# Arduino-DUE-V03A.net
KiCad netlist of a schematic drawn in EAGLE
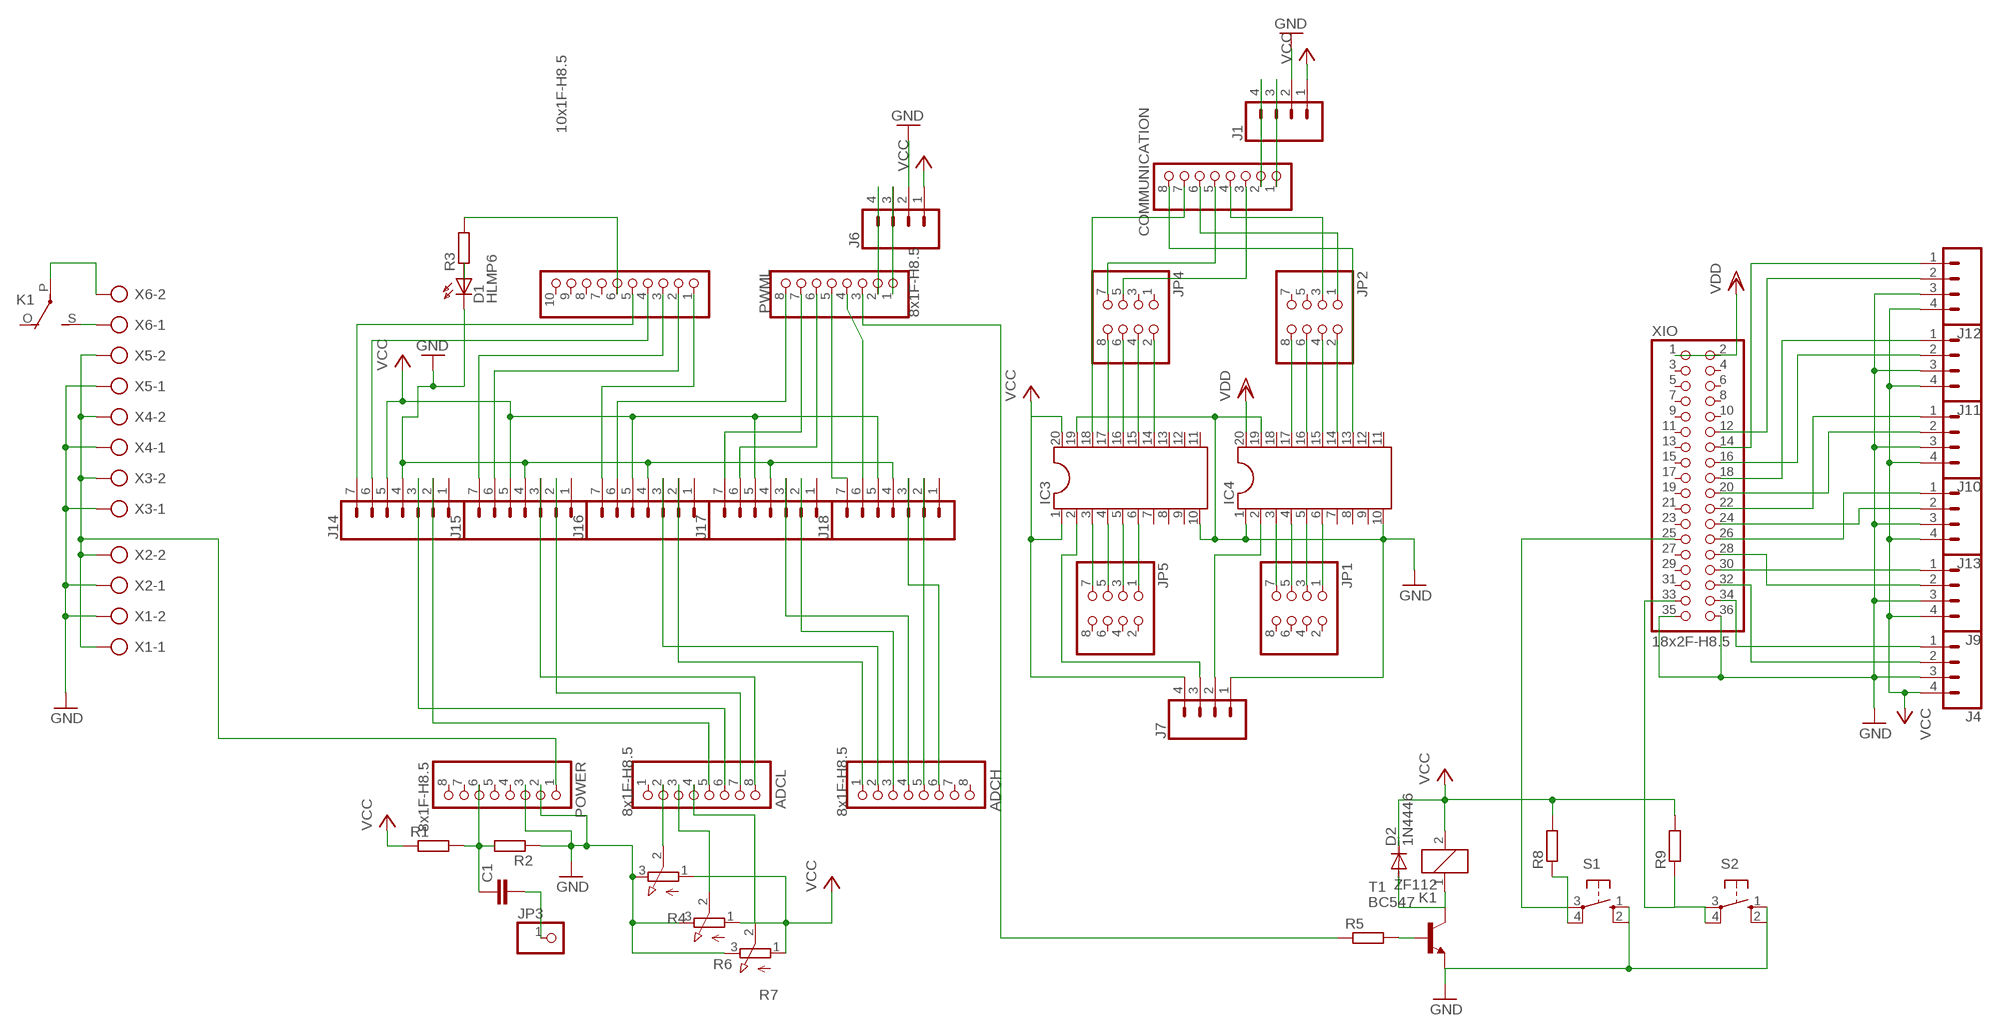
[diagram p0: schematic, sheet 1]

(export (version "E")
  (design (tool "Eeschema 10.0.6"))
  (components
    (comp (ref "ADCH")
      (value "8x1F-H8.5")
      (footprint "eagle-import:1X08")
      (libsource (lib "eagle-import") (part "PINHD-1X8"))
    )
    (comp (ref "ADCL")
      (value "8x1F-H8.5")
      (footprint "eagle-import:1X08")
      (libsource (lib "eagle-import") (part "PINHD-1X8"))
    )
    (comp (ref "C1")
      (value "C-EU025-025X050")
      (footprint "eagle-import:C025-025X050")
      (libsource (lib "eagle-import") (part "C-EU025-025X050"))
    )
    (comp (ref "COMMUNICATION")
      (value "8x1F-H8.5")
      (footprint "eagle-import:1X08")
      (libsource (lib "eagle-import") (part "PINHD-1X8"))
    )
    (comp (ref "D1")
      (value "HLMP6")
      (footprint "eagle-import:HLMP6")
      (fields (field (name "MF") "AGILENT TECHNOLOGIES") (field (name "MPN") "HLMP-6500"))
      (libsource (lib "eagle-import") (part "HLMP6"))
    )
    (comp (ref "D2")
      (value "1N4446")
      (footprint "eagle-import:DO35-10")
      (libsource (lib "eagle-import") (part "1N4446"))
    )
    (comp (ref "IC3")
      (value "DIL20S")
      (footprint "eagle-import:SOCKET-20")
      (libsource (lib "eagle-import") (part "DIL20S"))
    )
    (comp (ref "IC4")
      (value "DIL20S")
      (footprint "eagle-import:SOCKET-20")
      (libsource (lib "eagle-import") (part "DIL20S"))
    )
    (comp (ref "J1")
      (value "CONN_04LONGPADS")
      (footprint "eagle-import:1X04_LONGPADS")
      (libsource (lib "eagle-import") (part "CONN_04LONGPADS"))
    )
    (comp (ref "J4")
      (value "CONN_04LONGPADS")
      (footprint "eagle-import:1X04_LONGPADS")
      (libsource (lib "eagle-import") (part "CONN_04LONGPADS"))
    )
    (comp (ref "J6")
      (value "CONN_04LONGPADS")
      (footprint "eagle-import:1X04_LONGPADS")
      (libsource (lib "eagle-import") (part "CONN_04LONGPADS"))
    )
    (comp (ref "J7")
      (value "CONN_04LONGPADS")
      (footprint "eagle-import:1X04_LONGPADS")
      (libsource (lib "eagle-import") (part "CONN_04LONGPADS"))
    )
    (comp (ref "J9")
      (value "CONN_04LONGPADS")
      (footprint "eagle-import:1X04_LONGPADS")
      (libsource (lib "eagle-import") (part "CONN_04LONGPADS"))
    )
    (comp (ref "J10")
      (value "CONN_04LONGPADS")
      (footprint "eagle-import:1X04_LONGPADS")
      (libsource (lib "eagle-import") (part "CONN_04LONGPADS"))
    )
    (comp (ref "J11")
      (value "CONN_04LONGPADS")
      (footprint "eagle-import:1X04_LONGPADS")
      (libsource (lib "eagle-import") (part "CONN_04LONGPADS"))
    )
    (comp (ref "J12")
      (value "CONN_04LONGPADS")
      (footprint "eagle-import:1X04_LONGPADS")
      (libsource (lib "eagle-import") (part "CONN_04LONGPADS"))
    )
    (comp (ref "J13")
      (value "CONN_04LONGPADS")
      (footprint "eagle-import:1X04_LONGPADS")
      (libsource (lib "eagle-import") (part "CONN_04LONGPADS"))
    )
    (comp (ref "J14")
      (value "CONN_07LONGPADS")
      (footprint "eagle-import:1X07_LONGPADS")
      (libsource (lib "eagle-import") (part "CONN_07LONGPADS"))
    )
    (comp (ref "J15")
      (value "CONN_07LONGPADS")
      (footprint "eagle-import:1X07_LONGPADS")
      (libsource (lib "eagle-import") (part "CONN_07LONGPADS"))
    )
    (comp (ref "J16")
      (value "CONN_07LONGPADS")
      (footprint "eagle-import:1X07_LONGPADS")
      (libsource (lib "eagle-import") (part "CONN_07LONGPADS"))
    )
    (comp (ref "J17")
      (value "CONN_07LONGPADS")
      (footprint "eagle-import:1X07_LONGPADS")
      (libsource (lib "eagle-import") (part "CONN_07LONGPADS"))
    )
    (comp (ref "J18")
      (value "CONN_07LONGPADS")
      (footprint "eagle-import:1X07_LONGPADS")
      (libsource (lib "eagle-import") (part "CONN_07LONGPADS"))
    )
    (comp (ref "JP1")
      (value "PINHD-2X4")
      (footprint "eagle-import:2X04")
      (libsource (lib "eagle-import") (part "PINHD-2X4"))
    )
    (comp (ref "JP2")
      (value "PINHD-2X4")
      (footprint "eagle-import:2X04")
      (libsource (lib "eagle-import") (part "PINHD-2X4"))
    )
    (comp (ref "JP3")
      (value "PINHD-1X1")
      (footprint "eagle-import:1X01")
      (libsource (lib "eagle-import") (part "PINHD-1X1"))
    )
    (comp (ref "JP4")
      (value "PINHD-2X4")
      (footprint "eagle-import:2X04")
      (libsource (lib "eagle-import") (part "PINHD-2X4"))
    )
    (comp (ref "JP5")
      (value "PINHD-2X4")
      (footprint "eagle-import:2X04")
      (libsource (lib "eagle-import") (part "PINHD-2X4"))
    )
    (comp (ref "K1")
      (value "ZF112")
      (footprint "eagle-import:ZF112")
      (libsource (lib "eagle-import") (part "ZF112"))
    )
    (comp (ref "POWER")
      (value "8x1F-H8.5")
      (footprint "eagle-import:1X08")
      (libsource (lib "eagle-import") (part "PINHD-1X8"))
    )
    (comp (ref "PWMH")
      (value "10x1F-H8.5")
      (footprint "eagle-import:1X10")
      (libsource (lib "eagle-import") (part "PINHD-1X10"))
    )
    (comp (ref "PWML")
      (value "8x1F-H8.5")
      (footprint "eagle-import:1X08")
      (libsource (lib "eagle-import") (part "PINHD-1X8"))
    )
    (comp (ref "R1")
      (value "R-EU_0204/7")
      (footprint "eagle-import:0204_7")
      (libsource (lib "eagle-import") (part "R-EU_0204/7"))
    )
    (comp (ref "R2")
      (value "R-EU_0204/7")
      (footprint "eagle-import:0204_7")
      (libsource (lib "eagle-import") (part "R-EU_0204/7"))
    )
    (comp (ref "R3")
      (value "R-EU_0204/7")
      (footprint "eagle-import:0204_7")
      (libsource (lib "eagle-import") (part "R-EU_0204/7"))
    )
    (comp (ref "R4")
      (value "3RP/1610N")
      (footprint "eagle-import:3RP_1610N")
      (libsource (lib "eagle-import") (part "3RP/1610N"))
    )
    (comp (ref "R5")
      (value "R-EU_0204/7")
      (footprint "eagle-import:0204_7")
      (libsource (lib "eagle-import") (part "R-EU_0204/7"))
    )
    (comp (ref "R6")
      (value "3RP/1610N")
      (footprint "eagle-import:3RP_1610N")
      (libsource (lib "eagle-import") (part "3RP/1610N"))
    )
    (comp (ref "R7")
      (value "3RP/1610N")
      (footprint "eagle-import:3RP_1610N")
      (libsource (lib "eagle-import") (part "3RP/1610N"))
    )
    (comp (ref "R8")
      (value "R-EU_0204/7")
      (footprint "eagle-import:0204_7")
      (libsource (lib "eagle-import") (part "R-EU_0204/7"))
    )
    (comp (ref "R9")
      (value "R-EU_0204/7")
      (footprint "eagle-import:0204_7")
      (libsource (lib "eagle-import") (part "R-EU_0204/7"))
    )
    (comp (ref "S1")
      (value "10-XX")
      (footprint "eagle-import:B3F-10XX")
      (fields (field (name "MPN") "B3F-1000"))
      (libsource (lib "eagle-import") (part "10-XX"))
    )
    (comp (ref "S2")
      (value "10-XX")
      (footprint "eagle-import:B3F-10XX")
      (fields (field (name "MPN") "B3F-1000"))
      (libsource (lib "eagle-import") (part "10-XX"))
    )
    (comp (ref "T1")
      (value "BC547")
      (footprint "eagle-import:TO92")
      (libsource (lib "eagle-import") (part "BC547"))
    )
    (comp (ref "X1")
      (value "AK500/2")
      (footprint "eagle-import:AK500_2")
      (libsource (lib "eagle-import") (part "AK500/2"))
    )
    (comp (ref "X2")
      (value "AK500/2")
      (footprint "eagle-import:AK500_2")
      (libsource (lib "eagle-import") (part "AK500/2"))
    )
    (comp (ref "X3")
      (value "AK500/2")
      (footprint "eagle-import:AK500_2")
      (libsource (lib "eagle-import") (part "AK500/2"))
    )
    (comp (ref "X4")
      (value "AK500/2")
      (footprint "eagle-import:AK500_2")
      (libsource (lib "eagle-import") (part "AK500/2"))
    )
    (comp (ref "X5")
      (value "AK500/2")
      (footprint "eagle-import:AK500_2")
      (libsource (lib "eagle-import") (part "AK500/2"))
    )
    (comp (ref "X6")
      (value "AK500/2")
      (footprint "eagle-import:AK500_2")
      (libsource (lib "eagle-import") (part "AK500/2"))
    )
    (comp (ref "XIO")
      (value "18x2F-H8.5")
      (footprint "eagle-import:2X18")
      (libsource (lib "eagle-import") (part "PINHD-2X18"))
    )
  )
  (nets
    (net (code "1") (name "GND") (class "Default")
      (node (ref "D1") (pin "K") (pinfunction "K_K") (pintype "passive"))
      (node (ref "IC3") (pin "10") (pinfunction "10_10") (pintype "passive"))
      (node (ref "IC3") (pin "19") (pinfunction "19_19") (pintype "passive"))
      (node (ref "IC4") (pin "1") (pinfunction "1_1") (pintype "passive"))
      (node (ref "IC4") (pin "10") (pinfunction "10_10") (pintype "passive"))
      (node (ref "IC4") (pin "19") (pinfunction "19_19") (pintype "passive"))
      (node (ref "J1") (pin "2") (pinfunction "2_2") (pintype "passive"))
      (node (ref "J10") (pin "3") (pinfunction "3_3") (pintype "passive"))
      (node (ref "J11") (pin "3") (pinfunction "3_3") (pintype "passive"))
      (node (ref "J12") (pin "3") (pinfunction "3_3") (pintype "passive"))
      (node (ref "J13") (pin "3") (pinfunction "3_3") (pintype "passive"))
      (node (ref "J14") (pin "4") (pinfunction "4_4") (pintype "passive"))
      (node (ref "J15") (pin "4") (pinfunction "4_4") (pintype "passive"))
      (node (ref "J16") (pin "4") (pinfunction "4_4") (pintype "passive"))
      (node (ref "J17") (pin "4") (pinfunction "4_4") (pintype "passive"))
      (node (ref "J18") (pin "4") (pinfunction "4_4") (pintype "passive"))
      (node (ref "J4") (pin "3") (pinfunction "3_3") (pintype "passive"))
      (node (ref "J6") (pin "2") (pinfunction "2_2") (pintype "passive"))
      (node (ref "J7") (pin "1") (pinfunction "1_1") (pintype "passive"))
      (node (ref "J9") (pin "3") (pinfunction "3_3") (pintype "passive"))
      (node (ref "POWER") (pin "2") (pinfunction "2_2") (pintype "passive"))
      (node (ref "POWER") (pin "3") (pinfunction "3_3") (pintype "passive"))
      (node (ref "R2") (pin "1") (pinfunction "1_1") (pintype "passive"))
      (node (ref "R4") (pin "3") (pinfunction "E_3") (pintype "passive"))
      (node (ref "R6") (pin "3") (pinfunction "E_3") (pintype "passive"))
      (node (ref "R7") (pin "3") (pinfunction "E_3") (pintype "passive"))
      (node (ref "S1") (pin "1") (pinfunction "S_1") (pintype "passive"))
      (node (ref "S1") (pin "2") (pinfunction "S1_2") (pintype "passive"))
      (node (ref "S2") (pin "1") (pinfunction "S_1") (pintype "passive"))
      (node (ref "S2") (pin "2") (pinfunction "S1_2") (pintype "passive"))
      (node (ref "T1") (pin "1") (pinfunction "E_1") (pintype "passive"))
      (node (ref "X1") (pin "2") (pinfunction "KL_2") (pintype "passive"))
      (node (ref "X2") (pin "1") (pinfunction "KL_1") (pintype "passive"))
      (node (ref "X3") (pin "1") (pinfunction "KL_1") (pintype "passive"))
      (node (ref "X4") (pin "1") (pinfunction "KL_1") (pintype "passive"))
      (node (ref "X5") (pin "1") (pinfunction "KL_1") (pintype "passive"))
      (node (ref "XIO") (pin "35") (pinfunction "35_35") (pintype "passive"))
      (node (ref "XIO") (pin "36") (pinfunction "36_36") (pintype "passive"))
    )
    (net (code "2") (name "Net-(ADCH-Pad1)") (class "Default")
      (node (ref "ADCH") (pin "1") (pinfunction "1_1") (pintype "passive"))
      (node (ref "J16") (pin "2") (pinfunction "2_2") (pintype "passive"))
    )
    (net (code "3") (name "Net-(ADCH-Pad2)") (class "Default")
      (node (ref "ADCH") (pin "2") (pinfunction "2_2") (pintype "passive"))
      (node (ref "J16") (pin "3") (pinfunction "3_3") (pintype "passive"))
    )
    (net (code "4") (name "Net-(ADCH-Pad3)") (class "Default")
      (node (ref "ADCH") (pin "3") (pinfunction "3_3") (pintype "passive"))
      (node (ref "J17") (pin "2") (pinfunction "2_2") (pintype "passive"))
    )
    (net (code "5") (name "Net-(ADCH-Pad4)") (class "Default")
      (node (ref "ADCH") (pin "4") (pinfunction "4_4") (pintype "passive"))
      (node (ref "J17") (pin "3") (pinfunction "3_3") (pintype "passive"))
    )
    (net (code "6") (name "Net-(ADCH-Pad5)") (class "Default")
      (node (ref "ADCH") (pin "5") (pinfunction "5_5") (pintype "passive"))
      (node (ref "J18") (pin "2") (pinfunction "2_2") (pintype "passive"))
    )
    (net (code "7") (name "Net-(ADCH-Pad6)") (class "Default")
      (node (ref "ADCH") (pin "6") (pinfunction "6_6") (pintype "passive"))
      (node (ref "J18") (pin "3") (pinfunction "3_3") (pintype "passive"))
    )
    (net (code "8") (name "Net-(ADCL-Pad5)") (class "Default")
      (node (ref "ADCL") (pin "5") (pinfunction "5_5") (pintype "passive"))
      (node (ref "J14") (pin "2") (pinfunction "2_2") (pintype "passive"))
    )
    (net (code "9") (name "Net-(ADCL-Pad6)") (class "Default")
      (node (ref "ADCL") (pin "6") (pinfunction "6_6") (pintype "passive"))
      (node (ref "J14") (pin "3") (pinfunction "3_3") (pintype "passive"))
    )
    (net (code "10") (name "Net-(ADCL-Pad7)") (class "Default")
      (node (ref "ADCL") (pin "7") (pinfunction "7_7") (pintype "passive"))
      (node (ref "J15") (pin "2") (pinfunction "2_2") (pintype "passive"))
    )
    (net (code "11") (name "Net-(ADCL-Pad8)") (class "Default")
      (node (ref "ADCL") (pin "8") (pinfunction "8_8") (pintype "passive"))
      (node (ref "J15") (pin "3") (pinfunction "3_3") (pintype "passive"))
    )
    (net (code "12") (name "Net-(C1-Pad1)") (class "Default")
      (node (ref "C1") (pin "1") (pinfunction "1_1") (pintype "passive"))
      (node (ref "POWER") (pin "6") (pinfunction "6_6") (pintype "passive"))
      (node (ref "R1") (pin "2") (pinfunction "2_2") (pintype "passive"))
      (node (ref "R2") (pin "2") (pinfunction "2_2") (pintype "passive"))
    )
    (net (code "13") (name "Net-(C1-Pad2)") (class "Default")
      (node (ref "C1") (pin "2") (pinfunction "2_2") (pintype "passive"))
      (node (ref "JP3") (pin "1") (pinfunction "1_1") (pintype "passive"))
    )
    (net (code "14") (name "Net-(COMMUNICATION-Pad1)") (class "Default")
      (node (ref "COMMUNICATION") (pin "1") (pinfunction "1_1") (pintype "passive"))
      (node (ref "J1") (pin "3") (pinfunction "3_3") (pintype "passive"))
    )
    (net (code "15") (name "Net-(COMMUNICATION-Pad2)") (class "Default")
      (node (ref "COMMUNICATION") (pin "2") (pinfunction "2_2") (pintype "passive"))
      (node (ref "J1") (pin "4") (pinfunction "4_4") (pintype "passive"))
    )
    (net (code "16") (name "Net-(COMMUNICATION-Pad3)") (class "Default")
      (node (ref "COMMUNICATION") (pin "3") (pinfunction "3_3") (pintype "passive"))
      (node (ref "JP4") (pin "5") (pinfunction "5_5") (pintype "passive"))
    )
    (net (code "17") (name "Net-(COMMUNICATION-Pad4)") (class "Default")
      (node (ref "COMMUNICATION") (pin "4") (pinfunction "4_4") (pintype "passive"))
      (node (ref "JP2") (pin "3") (pinfunction "3_3") (pintype "passive"))
    )
    (net (code "18") (name "Net-(COMMUNICATION-Pad5)") (class "Default")
      (node (ref "COMMUNICATION") (pin "5") (pinfunction "5_5") (pintype "passive"))
      (node (ref "JP4") (pin "7") (pinfunction "7_7") (pintype "passive"))
    )
    (net (code "19") (name "Net-(COMMUNICATION-Pad6)") (class "Default")
      (node (ref "COMMUNICATION") (pin "6") (pinfunction "6_6") (pintype "passive"))
      (node (ref "JP2") (pin "1") (pinfunction "1_1") (pintype "passive"))
    )
    (net (code "20") (name "Net-(COMMUNICATION-Pad7)") (class "Default")
      (node (ref "COMMUNICATION") (pin "7") (pinfunction "7_7") (pintype "passive"))
      (node (ref "IC3") (pin "18") (pinfunction "18_18") (pintype "passive"))
    )
    (net (code "21") (name "Net-(COMMUNICATION-Pad8)") (class "Default")
      (node (ref "COMMUNICATION") (pin "8") (pinfunction "8_8") (pintype "passive"))
      (node (ref "IC4") (pin "13") (pinfunction "13_13") (pintype "passive"))
    )
    (net (code "22") (name "Net-(D1-PadA)") (class "Default")
      (node (ref "D1") (pin "A") (pinfunction "A_A") (pintype "passive"))
      (node (ref "R3") (pin "1") (pinfunction "1_1") (pintype "passive"))
    )
    (net (code "23") (name "Net-(IC3-Pad2)") (class "Default")
      (node (ref "IC3") (pin "2") (pinfunction "2_2") (pintype "passive"))
      (node (ref "J7") (pin "3") (pinfunction "3_3") (pintype "passive"))
    )
    (net (code "24") (name "Net-(IC3-Pad3)") (class "Default")
      (node (ref "IC3") (pin "3") (pinfunction "3_3") (pintype "passive"))
      (node (ref "JP5") (pin "7") (pinfunction "7_7") (pintype "passive"))
    )
    (net (code "25") (name "Net-(IC3-Pad4)") (class "Default")
      (node (ref "IC3") (pin "4") (pinfunction "4_4") (pintype "passive"))
      (node (ref "JP5") (pin "5") (pinfunction "5_5") (pintype "passive"))
    )
    (net (code "26") (name "Net-(IC3-Pad5)") (class "Default")
      (node (ref "IC3") (pin "5") (pinfunction "5_5") (pintype "passive"))
      (node (ref "JP5") (pin "3") (pinfunction "3_3") (pintype "passive"))
    )
    (net (code "27") (name "Net-(IC3-Pad6)") (class "Default")
      (node (ref "IC3") (pin "6") (pinfunction "6_6") (pintype "passive"))
      (node (ref "JP5") (pin "1") (pinfunction "1_1") (pintype "passive"))
    )
    (net (code "28") (name "Net-(IC3-Pad14)") (class "Default")
      (node (ref "IC3") (pin "14") (pinfunction "14_14") (pintype "passive"))
      (node (ref "JP4") (pin "2") (pinfunction "2_2") (pintype "passive"))
    )
    (net (code "29") (name "Net-(IC3-Pad15)") (class "Default")
      (node (ref "IC3") (pin "15") (pinfunction "15_15") (pintype "passive"))
      (node (ref "JP4") (pin "4") (pinfunction "4_4") (pintype "passive"))
    )
    (net (code "30") (name "Net-(IC3-Pad16)") (class "Default")
      (node (ref "IC3") (pin "16") (pinfunction "16_16") (pintype "passive"))
      (node (ref "JP4") (pin "6") (pinfunction "6_6") (pintype "passive"))
    )
    (net (code "31") (name "Net-(IC3-Pad17)") (class "Default")
      (node (ref "IC3") (pin "17") (pinfunction "17_17") (pintype "passive"))
      (node (ref "JP4") (pin "8") (pinfunction "8_8") (pintype "passive"))
    )
    (net (code "32") (name "Net-(IC4-Pad2)") (class "Default")
      (node (ref "IC4") (pin "2") (pinfunction "2_2") (pintype "passive"))
      (node (ref "J7") (pin "2") (pinfunction "2_2") (pintype "passive"))
    )
    (net (code "33") (name "Net-(IC4-Pad3)") (class "Default")
      (node (ref "IC4") (pin "3") (pinfunction "3_3") (pintype "passive"))
      (node (ref "JP1") (pin "7") (pinfunction "7_7") (pintype "passive"))
    )
    (net (code "34") (name "Net-(IC4-Pad4)") (class "Default")
      (node (ref "IC4") (pin "4") (pinfunction "4_4") (pintype "passive"))
      (node (ref "JP1") (pin "5") (pinfunction "5_5") (pintype "passive"))
    )
    (net (code "35") (name "Net-(IC4-Pad5)") (class "Default")
      (node (ref "IC4") (pin "5") (pinfunction "5_5") (pintype "passive"))
      (node (ref "JP1") (pin "3") (pinfunction "3_3") (pintype "passive"))
    )
    (net (code "36") (name "Net-(IC4-Pad6)") (class "Default")
      (node (ref "IC4") (pin "6") (pinfunction "6_6") (pintype "passive"))
      (node (ref "JP1") (pin "1") (pinfunction "1_1") (pintype "passive"))
    )
    (net (code "37") (name "Net-(IC4-Pad14)") (class "Default")
      (node (ref "IC4") (pin "14") (pinfunction "14_14") (pintype "passive"))
      (node (ref "JP2") (pin "2") (pinfunction "2_2") (pintype "passive"))
    )
    (net (code "38") (name "Net-(IC4-Pad15)") (class "Default")
      (node (ref "IC4") (pin "15") (pinfunction "15_15") (pintype "passive"))
      (node (ref "JP2") (pin "4") (pinfunction "4_4") (pintype "passive"))
    )
    (net (code "39") (name "Net-(IC4-Pad16)") (class "Default")
      (node (ref "IC4") (pin "16") (pinfunction "16_16") (pintype "passive"))
      (node (ref "JP2") (pin "6") (pinfunction "6_6") (pintype "passive"))
    )
    (net (code "40") (name "Net-(IC4-Pad17)") (class "Default")
      (node (ref "IC4") (pin "17") (pinfunction "17_17") (pintype "passive"))
      (node (ref "JP2") (pin "8") (pinfunction "8_8") (pintype "passive"))
    )
    (net (code "41") (name "Net-(J4-Pad1)") (class "Default")
      (node (ref "J4") (pin "1") (pinfunction "1_1") (pintype "passive"))
      (node (ref "XIO") (pin "34") (pinfunction "34_34") (pintype "passive"))
    )
    (net (code "42") (name "Net-(J4-Pad2)") (class "Default")
      (node (ref "J4") (pin "2") (pinfunction "2_2") (pintype "passive"))
      (node (ref "XIO") (pin "32") (pinfunction "32_32") (pintype "passive"))
    )
    (net (code "43") (name "Net-(J6-Pad3)") (class "Default")
      (node (ref "J6") (pin "3") (pinfunction "3_3") (pintype "passive"))
      (node (ref "PWML") (pin "1") (pinfunction "1_1") (pintype "passive"))
    )
    (net (code "44") (name "Net-(J6-Pad4)") (class "Default")
      (node (ref "J6") (pin "4") (pinfunction "4_4") (pintype "passive"))
      (node (ref "PWML") (pin "2") (pinfunction "2_2") (pintype "passive"))
    )
    (net (code "45") (name "Net-(J9-Pad1)") (class "Default")
      (node (ref "J9") (pin "1") (pinfunction "1_1") (pintype "passive"))
      (node (ref "XIO") (pin "30") (pinfunction "30_30") (pintype "passive"))
    )
    (net (code "46") (name "Net-(J9-Pad2)") (class "Default")
      (node (ref "J9") (pin "2") (pinfunction "2_2") (pintype "passive"))
      (node (ref "XIO") (pin "28") (pinfunction "28_28") (pintype "passive"))
    )
    (net (code "47") (name "Net-(J10-Pad1)") (class "Default")
      (node (ref "J10") (pin "1") (pinfunction "1_1") (pintype "passive"))
      (node (ref "XIO") (pin "22") (pinfunction "22_22") (pintype "passive"))
    )
    (net (code "48") (name "Net-(J10-Pad2)") (class "Default")
      (node (ref "J10") (pin "2") (pinfunction "2_2") (pintype "passive"))
      (node (ref "XIO") (pin "20") (pinfunction "20_20") (pintype "passive"))
    )
    (net (code "49") (name "Net-(J11-Pad1)") (class "Default")
      (node (ref "J11") (pin "1") (pinfunction "1_1") (pintype "passive"))
      (node (ref "XIO") (pin "18") (pinfunction "18_18") (pintype "passive"))
    )
    (net (code "50") (name "Net-(J11-Pad2)") (class "Default")
      (node (ref "J11") (pin "2") (pinfunction "2_2") (pintype "passive"))
      (node (ref "XIO") (pin "16") (pinfunction "16_16") (pintype "passive"))
    )
    (net (code "51") (name "Net-(J12-Pad1)") (class "Default")
      (node (ref "J12") (pin "1") (pinfunction "1_1") (pintype "passive"))
      (node (ref "XIO") (pin "14") (pinfunction "14_14") (pintype "passive"))
    )
    (net (code "52") (name "Net-(J12-Pad2)") (class "Default")
      (node (ref "J12") (pin "2") (pinfunction "2_2") (pintype "passive"))
      (node (ref "XIO") (pin "12") (pinfunction "12_12") (pintype "passive"))
    )
    (net (code "53") (name "Net-(J13-Pad1)") (class "Default")
      (node (ref "J13") (pin "1") (pinfunction "1_1") (pintype "passive"))
      (node (ref "XIO") (pin "26") (pinfunction "26_26") (pintype "passive"))
    )
    (net (code "54") (name "Net-(J13-Pad2)") (class "Default")
      (node (ref "J13") (pin "2") (pinfunction "2_2") (pintype "passive"))
      (node (ref "XIO") (pin "24") (pinfunction "24_24") (pintype "passive"))
    )
    (net (code "55") (name "Net-(J14-Pad6)") (class "Default")
      (node (ref "J14") (pin "6") (pinfunction "6_6") (pintype "passive"))
      (node (ref "PWMH") (pin "4") (pinfunction "4_4") (pintype "passive"))
    )
    (net (code "56") (name "Net-(J14-Pad7)") (class "Default")
      (node (ref "J14") (pin "7") (pinfunction "7_7") (pintype "passive"))
      (node (ref "PWMH") (pin "5") (pinfunction "5_5") (pintype "passive"))
    )
    (net (code "57") (name "Net-(J15-Pad6)") (class "Default")
      (node (ref "J15") (pin "6") (pinfunction "6_6") (pintype "passive"))
      (node (ref "PWMH") (pin "2") (pinfunction "2_2") (pintype "passive"))
    )
    (net (code "58") (name "Net-(J15-Pad7)") (class "Default")
      (node (ref "J15") (pin "7") (pinfunction "7_7") (pintype "passive"))
      (node (ref "PWMH") (pin "3") (pinfunction "3_3") (pintype "passive"))
    )
    (net (code "59") (name "Net-(J16-Pad6)") (class "Default")
      (node (ref "J16") (pin "6") (pinfunction "6_6") (pintype "passive"))
      (node (ref "PWML") (pin "8") (pinfunction "8_8") (pintype "passive"))
    )
    (net (code "60") (name "Net-(J16-Pad7)") (class "Default")
      (node (ref "J16") (pin "7") (pinfunction "7_7") (pintype "passive"))
      (node (ref "PWMH") (pin "1") (pinfunction "1_1") (pintype "passive"))
    )
    (net (code "61") (name "Net-(J17-Pad6)") (class "Default")
      (node (ref "J17") (pin "6") (pinfunction "6_6") (pintype "passive"))
      (node (ref "PWML") (pin "6") (pinfunction "6_6") (pintype "passive"))
    )
    (net (code "62") (name "Net-(J17-Pad7)") (class "Default")
      (node (ref "J17") (pin "7") (pinfunction "7_7") (pintype "passive"))
      (node (ref "PWML") (pin "7") (pinfunction "7_7") (pintype "passive"))
    )
    (net (code "63") (name "Net-(J18-Pad6)") (class "Default")
      (node (ref "J18") (pin "6") (pinfunction "6_6") (pintype "passive"))
      (node (ref "PWML") (pin "4") (pinfunction "4_4") (pintype "passive"))
    )
    (net (code "64") (name "Net-(J18-Pad7)") (class "Default")
      (node (ref "J18") (pin "7") (pinfunction "7_7") (pintype "passive"))
      (node (ref "PWML") (pin "5") (pinfunction "5_5") (pintype "passive"))
    )
    (net (code "65") (name "Net-(PWMH-Pad6)") (class "Default")
      (node (ref "PWMH") (pin "6") (pinfunction "6_6") (pintype "passive"))
      (node (ref "R3") (pin "2") (pinfunction "2_2") (pintype "passive"))
    )
    (net (code "66") (name "Net-(PWML-Pad3)") (class "Default")
      (node (ref "PWML") (pin "3") (pinfunction "3_3") (pintype "passive"))
      (node (ref "R5") (pin "1") (pinfunction "1_1") (pintype "passive"))
    )
    (net (code "67") (name "Net-(R4-S)") (class "Default")
      (node (ref "ADCL") (pin "2") (pinfunction "2_2") (pintype "passive"))
      (node (ref "R4") (pin "2") (pinfunction "S_2") (pintype "passive"))
    )
    (net (code "68") (name "Net-(R6-S)") (class "Default")
      (node (ref "ADCL") (pin "3") (pinfunction "3_3") (pintype "passive"))
      (node (ref "R6") (pin "2") (pinfunction "S_2") (pintype "passive"))
    )
    (net (code "69") (name "Net-(R7-S)") (class "Default")
      (node (ref "ADCL") (pin "4") (pinfunction "4_4") (pintype "passive"))
      (node (ref "R7") (pin "2") (pinfunction "S_2") (pintype "passive"))
    )
    (net (code "70") (name "Net-(S1-P)") (class "Default")
      (node (ref "R8") (pin "1") (pinfunction "1_1") (pintype "passive"))
      (node (ref "S1") (pin "3") (pinfunction "P_3") (pintype "passive"))
      (node (ref "S1") (pin "4") (pinfunction "P1_4") (pintype "passive"))
      (node (ref "XIO") (pin "25") (pinfunction "25_25") (pintype "passive"))
    )
    (net (code "71") (name "Net-(S2-P)") (class "Default")
      (node (ref "R9") (pin "1") (pinfunction "1_1") (pintype "passive"))
      (node (ref "S2") (pin "3") (pinfunction "P_3") (pintype "passive"))
      (node (ref "S2") (pin "4") (pinfunction "P1_4") (pintype "passive"))
      (node (ref "XIO") (pin "33") (pinfunction "33_33") (pintype "passive"))
    )
    (net (code "72") (name "Net-(T1-B)") (class "Default")
      (node (ref "R5") (pin "2") (pinfunction "2_2") (pintype "passive"))
      (node (ref "T1") (pin "2") (pinfunction "B_2") (pintype "passive"))
    )
    (net (code "73") (name "Net-(T1-C)") (class "Default")
      (node (ref "D2") (pin "A") (pinfunction "A_A") (pintype "passive"))
      (node (ref "K1") (pin "1") (pinfunction "1_1") (pintype "passive"))
      (node (ref "T1") (pin "3") (pinfunction "C_3") (pintype "passive"))
    )
    (net (code "74") (name "Net-(X1A-KL)") (class "Default")
      (node (ref "POWER") (pin "1") (pinfunction "1_1") (pintype "passive"))
      (node (ref "X1") (pin "1") (pinfunction "KL_1") (pintype "passive"))
      (node (ref "X2") (pin "2") (pinfunction "KL_2") (pintype "passive"))
      (node (ref "X3") (pin "2") (pinfunction "KL_2") (pintype "passive"))
      (node (ref "X4") (pin "2") (pinfunction "KL_2") (pintype "passive"))
      (node (ref "X5") (pin "2") (pinfunction "KL_2") (pintype "passive"))
    )
    (net (code "75") (name "Net-(X6A-KL)") (class "Default")
      (node (ref "K1") (pin "S") (pinfunction "S_S") (pintype "passive"))
      (node (ref "X6") (pin "1") (pinfunction "KL_1") (pintype "passive"))
    )
    (net (code "76") (name "Net-(X6B-KL)") (class "Default")
      (node (ref "K1") (pin "P") (pinfunction "P_P") (pintype "passive"))
      (node (ref "X6") (pin "2") (pinfunction "KL_2") (pintype "passive"))
    )
    (net (code "77") (name "VCC") (class "Default")
      (node (ref "D2") (pin "C") (pinfunction "C_C") (pintype "passive"))
      (node (ref "IC3") (pin "1") (pinfunction "1_1") (pintype "passive"))
      (node (ref "IC3") (pin "20") (pinfunction "20_20") (pintype "passive"))
      (node (ref "J1") (pin "1") (pinfunction "1_1") (pintype "passive"))
      (node (ref "J10") (pin "4") (pinfunction "4_4") (pintype "passive"))
      (node (ref "J11") (pin "4") (pinfunction "4_4") (pintype "passive"))
      (node (ref "J12") (pin "4") (pinfunction "4_4") (pintype "passive"))
      (node (ref "J13") (pin "4") (pinfunction "4_4") (pintype "passive"))
      (node (ref "J14") (pin "5") (pinfunction "5_5") (pintype "passive"))
      (node (ref "J15") (pin "5") (pinfunction "5_5") (pintype "passive"))
      (node (ref "J16") (pin "5") (pinfunction "5_5") (pintype "passive"))
      (node (ref "J17") (pin "5") (pinfunction "5_5") (pintype "passive"))
      (node (ref "J18") (pin "5") (pinfunction "5_5") (pintype "passive"))
      (node (ref "J4") (pin "4") (pinfunction "4_4") (pintype "passive"))
      (node (ref "J6") (pin "1") (pinfunction "1_1") (pintype "passive"))
      (node (ref "J7") (pin "4") (pinfunction "4_4") (pintype "passive"))
      (node (ref "J9") (pin "4") (pinfunction "4_4") (pintype "passive"))
      (node (ref "K1") (pin "2") (pinfunction "2_2") (pintype "passive"))
      (node (ref "R1") (pin "1") (pinfunction "1_1") (pintype "passive"))
      (node (ref "R4") (pin "1") (pinfunction "A_1") (pintype "passive"))
      (node (ref "R6") (pin "1") (pinfunction "A_1") (pintype "passive"))
      (node (ref "R7") (pin "1") (pinfunction "A_1") (pintype "passive"))
      (node (ref "R8") (pin "2") (pinfunction "2_2") (pintype "passive"))
      (node (ref "R9") (pin "2") (pinfunction "2_2") (pintype "passive"))
    )
    (net (code "78") (name "VDD") (class "Default")
      (node (ref "IC4") (pin "20") (pinfunction "20_20") (pintype "passive"))
      (node (ref "XIO") (pin "1") (pinfunction "1_1") (pintype "passive"))
      (node (ref "XIO") (pin "2") (pinfunction "2_2") (pintype "passive"))
    )
    (net (code "79") (name "unconnected-(ADCH-Pad7)") (class "Default")
      (node (ref "ADCH") (pin "7") (pinfunction "7_7") (pintype "passive"))
    )
    (net (code "80") (name "unconnected-(ADCH-Pad8)") (class "Default")
      (node (ref "ADCH") (pin "8") (pinfunction "8_8") (pintype "passive"))
    )
    (net (code "81") (name "unconnected-(ADCL-Pad1)") (class "Default")
      (node (ref "ADCL") (pin "1") (pinfunction "1_1") (pintype "passive"))
    )
    (net (code "82") (name "unconnected-(IC3-Pad7)") (class "Default")
      (node (ref "IC3") (pin "7") (pinfunction "7_7") (pintype "passive"))
    )
    (net (code "83") (name "unconnected-(IC3-Pad8)") (class "Default")
      (node (ref "IC3") (pin "8") (pinfunction "8_8") (pintype "passive"))
    )
    (net (code "84") (name "unconnected-(IC3-Pad9)") (class "Default")
      (node (ref "IC3") (pin "9") (pinfunction "9_9") (pintype "passive"))
    )
    (net (code "85") (name "unconnected-(IC3-Pad11)") (class "Default")
      (node (ref "IC3") (pin "11") (pinfunction "11_11") (pintype "passive"))
    )
    (net (code "86") (name "unconnected-(IC3-Pad12)") (class "Default")
      (node (ref "IC3") (pin "12") (pinfunction "12_12") (pintype "passive"))
    )
    (net (code "87") (name "unconnected-(IC3-Pad13)") (class "Default")
      (node (ref "IC3") (pin "13") (pinfunction "13_13") (pintype "passive"))
    )
    (net (code "88") (name "unconnected-(IC4-Pad7)") (class "Default")
      (node (ref "IC4") (pin "7") (pinfunction "7_7") (pintype "passive"))
    )
    (net (code "89") (name "unconnected-(IC4-Pad8)") (class "Default")
      (node (ref "IC4") (pin "8") (pinfunction "8_8") (pintype "passive"))
    )
    (net (code "90") (name "unconnected-(IC4-Pad9)") (class "Default")
      (node (ref "IC4") (pin "9") (pinfunction "9_9") (pintype "passive"))
    )
    (net (code "91") (name "unconnected-(IC4-Pad11)") (class "Default")
      (node (ref "IC4") (pin "11") (pinfunction "11_11") (pintype "passive"))
    )
    (net (code "92") (name "unconnected-(IC4-Pad12)") (class "Default")
      (node (ref "IC4") (pin "12") (pinfunction "12_12") (pintype "passive"))
    )
    (net (code "93") (name "unconnected-(IC4-Pad18)") (class "Default")
      (node (ref "IC4") (pin "18") (pinfunction "18_18") (pintype "passive"))
    )
    (net (code "94") (name "unconnected-(J14-Pad1)") (class "Default")
      (node (ref "J14") (pin "1") (pinfunction "1_1") (pintype "passive"))
    )
    (net (code "95") (name "unconnected-(J15-Pad1)") (class "Default")
      (node (ref "J15") (pin "1") (pinfunction "1_1") (pintype "passive"))
    )
    (net (code "96") (name "unconnected-(J16-Pad1)") (class "Default")
      (node (ref "J16") (pin "1") (pinfunction "1_1") (pintype "passive"))
    )
    (net (code "97") (name "unconnected-(J17-Pad1)") (class "Default")
      (node (ref "J17") (pin "1") (pinfunction "1_1") (pintype "passive"))
    )
    (net (code "98") (name "unconnected-(J18-Pad1)") (class "Default")
      (node (ref "J18") (pin "1") (pinfunction "1_1") (pintype "passive"))
    )
    (net (code "99") (name "unconnected-(JP1-Pad2)") (class "Default")
      (node (ref "JP1") (pin "2") (pinfunction "2_2") (pintype "passive"))
    )
    (net (code "100") (name "unconnected-(JP1-Pad4)") (class "Default")
      (node (ref "JP1") (pin "4") (pinfunction "4_4") (pintype "passive"))
    )
    (net (code "101") (name "unconnected-(JP1-Pad6)") (class "Default")
      (node (ref "JP1") (pin "6") (pinfunction "6_6") (pintype "passive"))
    )
    (net (code "102") (name "unconnected-(JP1-Pad8)") (class "Default")
      (node (ref "JP1") (pin "8") (pinfunction "8_8") (pintype "passive"))
    )
    (net (code "103") (name "unconnected-(JP2-Pad5)") (class "Default")
      (node (ref "JP2") (pin "5") (pinfunction "5_5") (pintype "passive"))
    )
    (net (code "104") (name "unconnected-(JP2-Pad7)") (class "Default")
      (node (ref "JP2") (pin "7") (pinfunction "7_7") (pintype "passive"))
    )
    (net (code "105") (name "unconnected-(JP4-Pad1)") (class "Default")
      (node (ref "JP4") (pin "1") (pinfunction "1_1") (pintype "passive"))
    )
    (net (code "106") (name "unconnected-(JP4-Pad3)") (class "Default")
      (node (ref "JP4") (pin "3") (pinfunction "3_3") (pintype "passive"))
    )
    (net (code "107") (name "unconnected-(JP5-Pad2)") (class "Default")
      (node (ref "JP5") (pin "2") (pinfunction "2_2") (pintype "passive"))
    )
    (net (code "108") (name "unconnected-(JP5-Pad4)") (class "Default")
      (node (ref "JP5") (pin "4") (pinfunction "4_4") (pintype "passive"))
    )
    (net (code "109") (name "unconnected-(JP5-Pad6)") (class "Default")
      (node (ref "JP5") (pin "6") (pinfunction "6_6") (pintype "passive"))
    )
    (net (code "110") (name "unconnected-(JP5-Pad8)") (class "Default")
      (node (ref "JP5") (pin "8") (pinfunction "8_8") (pintype "passive"))
    )
    (net (code "111") (name "unconnected-(K1-PadO)") (class "Default")
      (node (ref "K1") (pin "O") (pinfunction "O_O") (pintype "passive"))
    )
    (net (code "112") (name "unconnected-(POWER-Pad4)") (class "Default")
      (node (ref "POWER") (pin "4") (pinfunction "4_4") (pintype "passive"))
    )
    (net (code "113") (name "unconnected-(POWER-Pad5)") (class "Default")
      (node (ref "POWER") (pin "5") (pinfunction "5_5") (pintype "passive"))
    )
    (net (code "114") (name "unconnected-(POWER-Pad7)") (class "Default")
      (node (ref "POWER") (pin "7") (pinfunction "7_7") (pintype "passive"))
    )
    (net (code "115") (name "unconnected-(POWER-Pad8)") (class "Default")
      (node (ref "POWER") (pin "8") (pinfunction "8_8") (pintype "passive"))
    )
    (net (code "116") (name "unconnected-(PWMH-Pad7)") (class "Default")
      (node (ref "PWMH") (pin "7") (pinfunction "7_7") (pintype "passive"))
    )
    (net (code "117") (name "unconnected-(PWMH-Pad8)") (class "Default")
      (node (ref "PWMH") (pin "8") (pinfunction "8_8") (pintype "passive"))
    )
    (net (code "118") (name "unconnected-(PWMH-Pad9)") (class "Default")
      (node (ref "PWMH") (pin "9") (pinfunction "9_9") (pintype "passive"))
    )
    (net (code "119") (name "unconnected-(PWMH-Pad10)") (class "Default")
      (node (ref "PWMH") (pin "10") (pinfunction "10_10") (pintype "passive"))
    )
    (net (code "120") (name "unconnected-(XIO-Pad3)") (class "Default")
      (node (ref "XIO") (pin "3") (pinfunction "3_3") (pintype "passive"))
    )
    (net (code "121") (name "unconnected-(XIO-Pad4)") (class "Default")
      (node (ref "XIO") (pin "4") (pinfunction "4_4") (pintype "passive"))
    )
    (net (code "122") (name "unconnected-(XIO-Pad5)") (class "Default")
      (node (ref "XIO") (pin "5") (pinfunction "5_5") (pintype "passive"))
    )
    (net (code "123") (name "unconnected-(XIO-Pad6)") (class "Default")
      (node (ref "XIO") (pin "6") (pinfunction "6_6") (pintype "passive"))
    )
    (net (code "124") (name "unconnected-(XIO-Pad7)") (class "Default")
      (node (ref "XIO") (pin "7") (pinfunction "7_7") (pintype "passive"))
    )
    (net (code "125") (name "unconnected-(XIO-Pad8)") (class "Default")
      (node (ref "XIO") (pin "8") (pinfunction "8_8") (pintype "passive"))
    )
    (net (code "126") (name "unconnected-(XIO-Pad9)") (class "Default")
      (node (ref "XIO") (pin "9") (pinfunction "9_9") (pintype "passive"))
    )
    (net (code "127") (name "unconnected-(XIO-Pad10)") (class "Default")
      (node (ref "XIO") (pin "10") (pinfunction "10_10") (pintype "passive"))
    )
    (net (code "128") (name "unconnected-(XIO-Pad11)") (class "Default")
      (node (ref "XIO") (pin "11") (pinfunction "11_11") (pintype "passive"))
    )
    (net (code "129") (name "unconnected-(XIO-Pad13)") (class "Default")
      (node (ref "XIO") (pin "13") (pinfunction "13_13") (pintype "passive"))
    )
    (net (code "130") (name "unconnected-(XIO-Pad15)") (class "Default")
      (node (ref "XIO") (pin "15") (pinfunction "15_15") (pintype "passive"))
    )
    (net (code "131") (name "unconnected-(XIO-Pad17)") (class "Default")
      (node (ref "XIO") (pin "17") (pinfunction "17_17") (pintype "passive"))
    )
    (net (code "132") (name "unconnected-(XIO-Pad19)") (class "Default")
      (node (ref "XIO") (pin "19") (pinfunction "19_19") (pintype "passive"))
    )
    (net (code "133") (name "unconnected-(XIO-Pad21)") (class "Default")
      (node (ref "XIO") (pin "21") (pinfunction "21_21") (pintype "passive"))
    )
    (net (code "134") (name "unconnected-(XIO-Pad23)") (class "Default")
      (node (ref "XIO") (pin "23") (pinfunction "23_23") (pintype "passive"))
    )
    (net (code "135") (name "unconnected-(XIO-Pad27)") (class "Default")
      (node (ref "XIO") (pin "27") (pinfunction "27_27") (pintype "passive"))
    )
    (net (code "136") (name "unconnected-(XIO-Pad29)") (class "Default")
      (node (ref "XIO") (pin "29") (pinfunction "29_29") (pintype "passive"))
    )
    (net (code "137") (name "unconnected-(XIO-Pad31)") (class "Default")
      (node (ref "XIO") (pin "31") (pinfunction "31_31") (pintype "passive"))
    )
  )
)
